# PS3604LD.net
KiCad netlist of a schematic drawn in Altium Designer
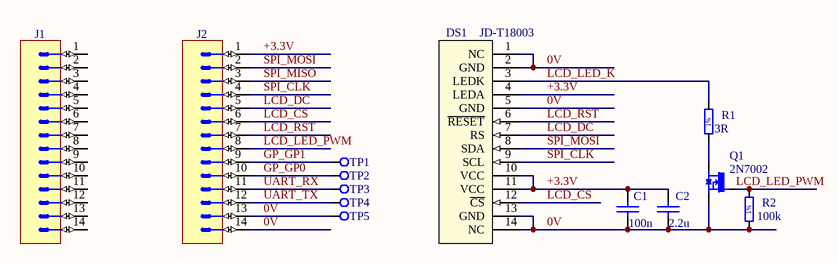
[diagram p0: PS3604LD.SchDoc]

(export (version "E")
  (design (tool "Eeschema 10.0.6"))
  (components
    (comp (ref "C1")
      (value "100n")
      (footprint "CAPC1005X55N")
      (description "Non-polarised capacitor")
      (fields
        (field (name "PART NUMBER") "CC0402_100NF_16V_10%_X7R")
        (field (name "VOLTAGE") "16V")
        (field (name "AUTHOR") "CERN DEM JLC")
      )
      (libsource (lib "Capacitors") (part "Capacitor - non polarized"))
    )
    (comp (ref "C2")
      (value "2.2u")
      (footprint "CAPC1005X55N")
      (description "Non-polarised capacitor")
      (fields
        (field (name "PART NUMBER") "CC0402_2.2UF_6.3V_20%_X5R")
        (field (name "VOLTAGE") "6.3V")
        (field (name "AUTHOR") "ELMAN")
      )
      (libsource (lib "Capacitors") (part "Capacitor - non polarized"))
    )
    (comp (ref "DS1")
      (value "JD-T18003")
      (footprint "JD_T18003")
      (fields
        (field (name "PART NUMBER") "JD_T18003")
        (field (name "MANUFACTURER") "Truly Semiconductors Inc.")
        (field (name "MANUFACTURER PART NUMBER") "JD-T18003-T01")
        (field (name "AUTHOR") "DEL")
      )
      (libsource (lib "ICs And Semiconductors") (part "JD_T18003"))
    )
    (comp (ref "J1")
      (value "Socket 14")
      (footprint "3M_951114-8622-AR")
      (description "Connector 14 Male")
      (fields
        (field (name "PART NUMBER") "3M_951114-8622-AR")
        (field (name "MANUFACTURER") "3M")
        (field (name "AUTHOR") "DEL")
      )
      (libsource (lib "Connectors") (part "Connector 14 Male"))
    )
    (comp (ref "J2")
      (value "Socket 14")
      (footprint "3M_951114-8622-AR")
      (description "Connector 14 Male")
      (fields
        (field (name "PART NUMBER") "3M_951114-8622-AR")
        (field (name "MANUFACTURER") "3M")
        (field (name "AUTHOR") "DEL")
      )
      (libsource (lib "Connectors") (part "Connector 14 Male"))
    )
    (comp (ref "Q1")
      (value "2N7002")
      (footprint "SOT95P240X130-3N")
      (description "N-CHANNEL MOSFET WITH DIODE")
      (fields (field (name "MANUFACTURER") "FAIRCHILD SEMICONDUCTOR") (field (name "AUTHOR") "CERN DEM JLC"))
      (libsource (lib "ICs And Semiconductors") (part "N-MOSFET-D 1G 2S 3D"))
    )
    (comp (ref "R1")
      (value "3R")
      (footprint "RESC2012X60N")
      (description "Resistor - 1%")
      (fields
        (field (name "PART NUMBER") "R0805_3R_1%_0.125W_200PPM")
        (field (name "POWER") "0.125W")
        (field (name "AUTHOR") "CERN DEM JLC")
      )
      (libsource (lib "Resistors") (part "Resistor - 1%"))
    )
    (comp (ref "R2")
      (value "100k")
      (footprint "RESC1005X40N")
      (description "Resistor - 1%")
      (fields
        (field (name "PART NUMBER") "R0402_100K_1%_0.0625W_100PPM")
        (field (name "POWER") "0.0625W")
        (field (name "AUTHOR") "CERN DEM JLC")
      )
      (libsource (lib "Resistors") (part "Resistor - 1%"))
    )
    (comp (ref "TP1")
      (value "Test Point")
      (footprint "TP_SMD_800")
      (fields (field (name "PART NUMBER") "TP_SMD_0.8MM") (field (name "AUTHOR") "DEL"))
      (libsource (lib "Eletro-mechanical") (part "Test Point"))
    )
    (comp (ref "TP2")
      (value "Test Point")
      (footprint "TP_SMD_800")
      (fields (field (name "PART NUMBER") "TP_SMD_0.8MM") (field (name "AUTHOR") "DEL"))
      (libsource (lib "Eletro-mechanical") (part "Test Point"))
    )
    (comp (ref "TP3")
      (value "Test Point")
      (footprint "TP_SMD_800")
      (fields (field (name "PART NUMBER") "TP_SMD_0.8MM") (field (name "AUTHOR") "DEL"))
      (libsource (lib "Eletro-mechanical") (part "Test Point"))
    )
    (comp (ref "TP4")
      (value "Test Point")
      (footprint "TP_SMD_800")
      (fields (field (name "PART NUMBER") "TP_SMD_0.8MM") (field (name "AUTHOR") "DEL"))
      (libsource (lib "Eletro-mechanical") (part "Test Point"))
    )
    (comp (ref "TP5")
      (value "Test Point")
      (footprint "TP_SMD_800")
      (fields (field (name "PART NUMBER") "TP_SMD_0.8MM") (field (name "AUTHOR") "DEL"))
      (libsource (lib "Eletro-mechanical") (part "Test Point"))
    )
  )
  (nets
    (net (code "1") (name "/+3.3V") (class "Default")
      (node (ref "C1") (pin "2") (pinfunction "2_2") (pintype "passive"))
      (node (ref "C2") (pin "2") (pinfunction "2_2") (pintype "passive"))
      (node (ref "DS1") (pin "10") (pinfunction "VCC_10") (pintype "power_in"))
      (node (ref "DS1") (pin "11") (pinfunction "VCC_11") (pintype "power_in"))
      (node (ref "DS1") (pin "4") (pinfunction "LEDA_4") (pintype "power_in"))
      (node (ref "J2") (pin "1") (pinfunction "1_1") (pintype "bidirectional"))
    )
    (net (code "2") (name "/0V") (class "Default")
      (node (ref "C1") (pin "1") (pinfunction "1_1") (pintype "passive"))
      (node (ref "C2") (pin "1") (pinfunction "1_1") (pintype "passive"))
      (node (ref "DS1") (pin "1") (pinfunction "NC_1") (pintype "passive"))
      (node (ref "DS1") (pin "13") (pinfunction "GND_13") (pintype "power_in"))
      (node (ref "DS1") (pin "14") (pinfunction "NC_14") (pintype "passive"))
      (node (ref "DS1") (pin "2") (pinfunction "GND_2") (pintype "power_in"))
      (node (ref "DS1") (pin "5") (pinfunction "GND_5") (pintype "power_in"))
      (node (ref "J2") (pin "13") (pinfunction "13_13") (pintype "bidirectional"))
      (node (ref "J2") (pin "14") (pinfunction "14_14") (pintype "bidirectional"))
      (node (ref "Q1") (pin "2") (pinfunction "S_2") (pintype "passive"))
      (node (ref "R2") (pin "1") (pinfunction "1_1") (pintype "passive"))
      (node (ref "TP5") (pin "1") (pinfunction "1_1") (pintype "passive"))
    )
    (net (code "3") (name "/GP_GP0") (class "Default")
      (node (ref "J2") (pin "10") (pinfunction "10_10") (pintype "bidirectional"))
      (node (ref "TP2") (pin "1") (pinfunction "1_1") (pintype "passive"))
    )
    (net (code "4") (name "/GP_GP1") (class "Default")
      (node (ref "J2") (pin "9") (pinfunction "9_9") (pintype "bidirectional"))
      (node (ref "TP1") (pin "1") (pinfunction "1_1") (pintype "passive"))
    )
    (net (code "5") (name "/LCD_CS") (class "Default")
      (node (ref "DS1") (pin "12") (pinfunction "~{CS}_12") (pintype "input"))
      (node (ref "J2") (pin "6") (pinfunction "6_6") (pintype "bidirectional"))
    )
    (net (code "6") (name "/LCD_DC") (class "Default")
      (node (ref "DS1") (pin "7") (pinfunction "RS_7") (pintype "input"))
      (node (ref "J2") (pin "5") (pinfunction "5_5") (pintype "bidirectional"))
    )
    (net (code "7") (name "/LCD_LED_K") (class "Default")
      (node (ref "DS1") (pin "3") (pinfunction "LEDK_3") (pintype "power_in"))
      (node (ref "R1") (pin "2") (pinfunction "2_2") (pintype "passive"))
    )
    (net (code "8") (name "/LCD_LED_PWM") (class "Default")
      (node (ref "J2") (pin "8") (pinfunction "8_8") (pintype "bidirectional"))
      (node (ref "Q1") (pin "1") (pinfunction "G_1") (pintype "passive"))
      (node (ref "R2") (pin "2") (pinfunction "2_2") (pintype "passive"))
    )
    (net (code "9") (name "/LCD_RST") (class "Default")
      (node (ref "DS1") (pin "6") (pinfunction "~{RESET}_6") (pintype "input"))
      (node (ref "J2") (pin "7") (pinfunction "7_7") (pintype "bidirectional"))
    )
    (net (code "10") (name "/SPI_CLK") (class "Default")
      (node (ref "DS1") (pin "9") (pinfunction "SCL_9") (pintype "input"))
      (node (ref "J2") (pin "4") (pinfunction "4_4") (pintype "bidirectional"))
    )
    (net (code "11") (name "/SPI_MISO") (class "Default")
      (node (ref "J2") (pin "3") (pinfunction "3_3") (pintype "bidirectional"))
    )
    (net (code "12") (name "/SPI_MOSI") (class "Default")
      (node (ref "DS1") (pin "8") (pinfunction "SDA_8") (pintype "input"))
      (node (ref "J2") (pin "2") (pinfunction "2_2") (pintype "bidirectional"))
    )
    (net (code "13") (name "/UART_RX") (class "Default")
      (node (ref "J2") (pin "11") (pinfunction "11_11") (pintype "bidirectional"))
      (node (ref "TP3") (pin "1") (pinfunction "1_1") (pintype "passive"))
    )
    (net (code "14") (name "/UART_TX") (class "Default")
      (node (ref "J2") (pin "12") (pinfunction "12_12") (pintype "bidirectional"))
      (node (ref "TP4") (pin "1") (pinfunction "1_1") (pintype "passive"))
    )
    (net (code "15") (name "Net-(Q1-D)") (class "Default")
      (node (ref "Q1") (pin "3") (pinfunction "D_3") (pintype "passive"))
      (node (ref "R1") (pin "1") (pinfunction "1_1") (pintype "passive"))
    )
    (net (code "16") (name "unconnected-(J1-Pad1)") (class "Default")
      (node (ref "J1") (pin "1") (pinfunction "1_1") (pintype "bidirectional"))
    )
    (net (code "17") (name "unconnected-(J1-Pad2)") (class "Default")
      (node (ref "J1") (pin "2") (pinfunction "2_2") (pintype "bidirectional"))
    )
    (net (code "18") (name "unconnected-(J1-Pad3)") (class "Default")
      (node (ref "J1") (pin "3") (pinfunction "3_3") (pintype "bidirectional"))
    )
    (net (code "19") (name "unconnected-(J1-Pad4)") (class "Default")
      (node (ref "J1") (pin "4") (pinfunction "4_4") (pintype "bidirectional"))
    )
    (net (code "20") (name "unconnected-(J1-Pad5)") (class "Default")
      (node (ref "J1") (pin "5") (pinfunction "5_5") (pintype "bidirectional"))
    )
    (net (code "21") (name "unconnected-(J1-Pad6)") (class "Default")
      (node (ref "J1") (pin "6") (pinfunction "6_6") (pintype "bidirectional"))
    )
    (net (code "22") (name "unconnected-(J1-Pad7)") (class "Default")
      (node (ref "J1") (pin "7") (pinfunction "7_7") (pintype "bidirectional"))
    )
    (net (code "23") (name "unconnected-(J1-Pad8)") (class "Default")
      (node (ref "J1") (pin "8") (pinfunction "8_8") (pintype "bidirectional"))
    )
    (net (code "24") (name "unconnected-(J1-Pad9)") (class "Default")
      (node (ref "J1") (pin "9") (pinfunction "9_9") (pintype "bidirectional"))
    )
    (net (code "25") (name "unconnected-(J1-Pad10)") (class "Default")
      (node (ref "J1") (pin "10") (pinfunction "10_10") (pintype "bidirectional"))
    )
    (net (code "26") (name "unconnected-(J1-Pad11)") (class "Default")
      (node (ref "J1") (pin "11") (pinfunction "11_11") (pintype "bidirectional"))
    )
    (net (code "27") (name "unconnected-(J1-Pad12)") (class "Default")
      (node (ref "J1") (pin "12") (pinfunction "12_12") (pintype "bidirectional"))
    )
    (net (code "28") (name "unconnected-(J1-Pad13)") (class "Default")
      (node (ref "J1") (pin "13") (pinfunction "13_13") (pintype "bidirectional"))
    )
    (net (code "29") (name "unconnected-(J1-Pad14)") (class "Default")
      (node (ref "J1") (pin "14") (pinfunction "14_14") (pintype "bidirectional"))
    )
  )
)
